# MAIN.net
KiCad netlist of a schematic drawn in Altium Designer
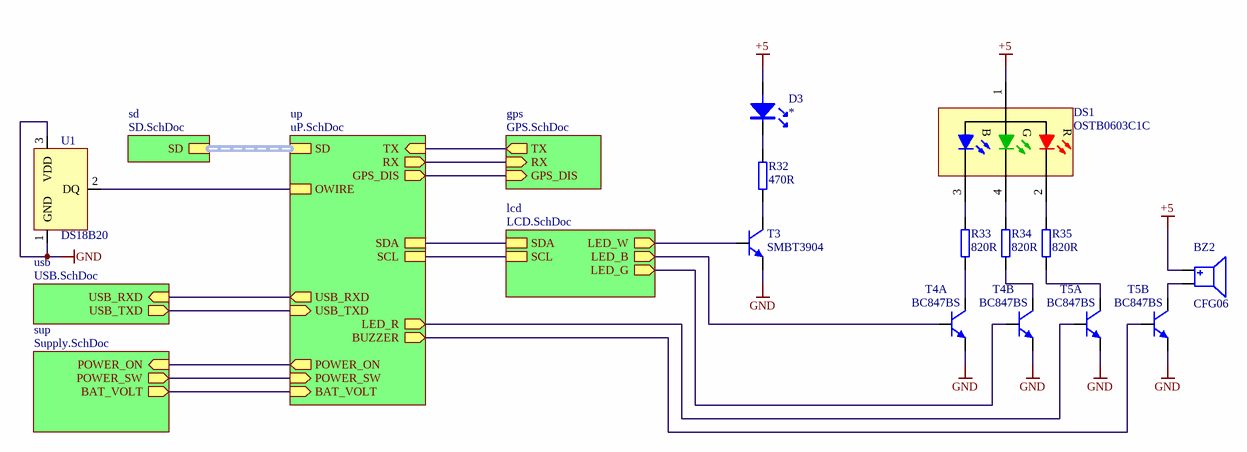
[diagram p0: MAIN.SchDoc]

(export (version "E")
  (design (tool "Eeschema 10.0.6"))
  (components
    (comp (ref "BZ2")
      (value "CFG06")
      (footprint "CFG-06")
      (description "BUZZER;")
      (libsource (lib "SONEL_all") (part "CFG06"))
    )
    (comp (ref "D3")
      (value "*")
      (footprint "LED_0805")
      (description "LED;")
      (libsource (lib "SONEL_all") (part "LED"))
    )
    (comp (ref "DS1")
      (value "OSTB0603C1C")
      (footprint "LED0603_4")
      (description "LED, RGB, SMD")
      (libsource (lib "SONEL_all") (part "OPTOSUPPLY OSTB0603C1C"))
    )
    (comp (ref "R32")
      (value "470R")
      (footprint "R0805")
      (description "R; resistor")
      (libsource (lib "SONEL_all") (part "R"))
    )
    (comp (ref "R33")
      (value "820R")
      (footprint "R0805")
      (description "R; resistor")
      (libsource (lib "SONEL_all") (part "R"))
    )
    (comp (ref "R34")
      (value "820R")
      (footprint "R0805")
      (description "R; resistor")
      (libsource (lib "SONEL_all") (part "R"))
    )
    (comp (ref "R35")
      (value "820R")
      (footprint "R0805")
      (description "R; resistor")
      (libsource (lib "SONEL_all") (part "R"))
    )
    (comp (ref "T3")
      (value "SMBT3904")
      (footprint "SOT23J")
      (description "T_NPN; Bipolar Transistor")
      (libsource (lib "SONEL_all") (part "SMBT3904"))
    )
    (comp (ref "T4")
      (value "BC847BS")
      (footprint "SOT363")
      (description "T_NPN; Bipolar Transistor")
      (libsource (lib "SONEL_all") (part "BC847BS"))
    )
    (comp (ref "T5")
      (value "BC847BS")
      (footprint "SOT363")
      (description "T_NPN; Bipolar Transistor")
      (libsource (lib "SONEL_all") (part "BC847BS"))
    )
    (comp (ref "U1")
      (value "DS18B20")
      (footprint "TO-92")
      (description "temperature sensor")
      (libsource (lib "SONEL_all") (part "DS18B20"))
    )
  )
  (nets
    (net (code "1") (name "+5") (class "Default")
      (node (ref "BZ2") (pin "+") (pintype "passive"))
      (node (ref "D3") (pin "A") (pinfunction "A_A") (pintype "passive"))
      (node (ref "DS1") (pin "1") (pinfunction "A2_1") (pintype "passive"))
    )
    (net (code "3") (name "/BUZZER") (class "Default")
      (node (ref "T5") (pin "5") (pinfunction "B2_5") (pintype "passive"))
    )
    (net (code "5") (name "/LED_B") (class "Default")
      (node (ref "T4") (pin "2") (pinfunction "B1_2") (pintype "passive"))
    )
    (net (code "6") (name "/LED_G") (class "Default")
      (node (ref "T4") (pin "5") (pinfunction "B2_5") (pintype "passive"))
    )
    (net (code "7") (name "/LED_R") (class "Default")
      (node (ref "T5") (pin "2") (pinfunction "B1_2") (pintype "passive"))
    )
    (net (code "8") (name "/LED_W") (class "Default")
      (node (ref "T3") (pin "2") (pinfunction "B_2") (pintype "passive"))
    )
    (net (code "9") (name "/OWIRE") (class "Default")
      (node (ref "U1") (pin "2") (pinfunction "DQ_2") (pintype "open_collector"))
    )
    (net (code "19") (name "GND") (class "Default")
      (node (ref "T3") (pin "1") (pinfunction "E_1") (pintype "passive"))
      (node (ref "T4") (pin "1") (pinfunction "E1_1") (pintype "passive"))
      (node (ref "T4") (pin "4") (pinfunction "E2_4") (pintype "passive"))
      (node (ref "T5") (pin "1") (pinfunction "E1_1") (pintype "passive"))
      (node (ref "T5") (pin "4") (pinfunction "E2_4") (pintype "passive"))
      (node (ref "U1") (pin "1") (pinfunction "GND_1") (pintype "power_in"))
      (node (ref "U1") (pin "3") (pinfunction "VDD_3") (pintype "power_in"))
    )
    (net (code "20") (name "Net-(D3-PadK)") (class "Default")
      (node (ref "D3") (pin "K") (pinfunction "K_K") (pintype "passive"))
      (node (ref "R32") (pin "2") (pintype "passive"))
    )
    (net (code "21") (name "Net-(DS1-B)") (class "Default")
      (node (ref "DS1") (pin "3") (pinfunction "B_3") (pintype "passive"))
      (node (ref "R33") (pin "1") (pintype "passive"))
    )
    (net (code "22") (name "Net-(DS1-G)") (class "Default")
      (node (ref "DS1") (pin "4") (pinfunction "G_4") (pintype "passive"))
      (node (ref "R34") (pin "1") (pintype "passive"))
    )
    (net (code "23") (name "Net-(DS1-R)") (class "Default")
      (node (ref "DS1") (pin "2") (pinfunction "R_2") (pintype "passive"))
      (node (ref "R35") (pin "1") (pintype "passive"))
    )
    (net (code "24") (name "Net-(T3-C)") (class "Default")
      (node (ref "R32") (pin "1") (pintype "passive"))
      (node (ref "T3") (pin "3") (pinfunction "C_3") (pintype "passive"))
    )
    (net (code "25") (name "Net-(T4A-C1)") (class "Default")
      (node (ref "R33") (pin "2") (pintype "passive"))
      (node (ref "T4") (pin "3") (pinfunction "C1_3") (pintype "passive"))
    )
    (net (code "26") (name "Net-(T4B-C2)") (class "Default")
      (node (ref "R34") (pin "2") (pintype "passive"))
      (node (ref "T4") (pin "6") (pinfunction "C2_6") (pintype "passive"))
    )
    (net (code "27") (name "Net-(T5A-C1)") (class "Default")
      (node (ref "R35") (pin "2") (pintype "passive"))
      (node (ref "T5") (pin "3") (pinfunction "C1_3") (pintype "passive"))
    )
    (net (code "28") (name "Net-(T5B-C2)") (class "Default")
      (node (ref "BZ2") (pin "-") (pintype "passive"))
      (node (ref "T5") (pin "6") (pinfunction "C2_6") (pintype "passive"))
    )
  )
)
